# Sheet1.net
KiCad netlist of a schematic drawn in Altium Designer
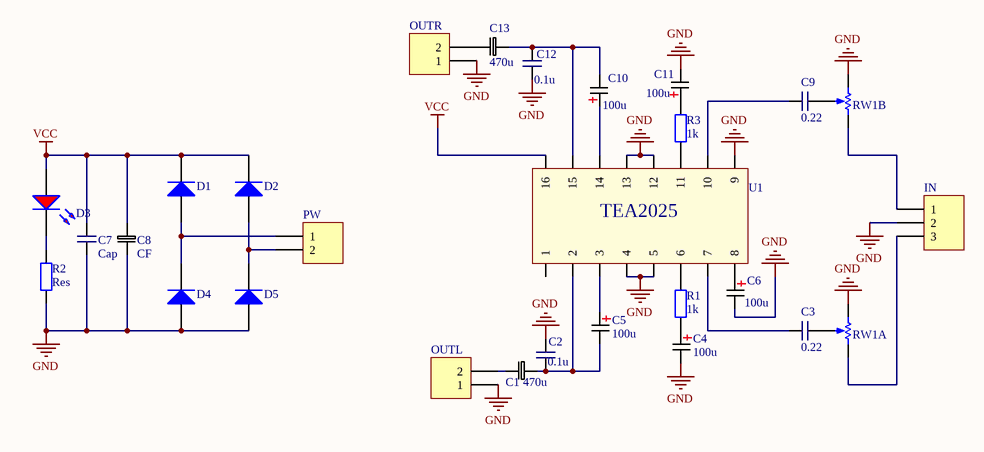
[diagram p0: Sheet1.SchDoc]

(export (version "E")
  (design (tool "Eeschema 10.0.6"))
  (components
    (comp (ref "C1") (value "470u") (footprint "CF0.1-6.5") (libsource (lib "MY") (part "CF")))
    (comp (ref "C2") (value "0.1u") (footprint "RAD0.1") (libsource (lib "MY") (part "Cap")))
    (comp (ref "C3") (value "0.22") (footprint "RAD-0.2") (libsource (lib "MY") (part "Cap")))
    (comp (ref "C4") (value "100u") (footprint "CF0.1") (libsource (lib "MY") (part "Cap Pol")))
    (comp (ref "C5") (value "100u") (footprint "CF0.1") (libsource (lib "MY") (part "Cap Pol")))
    (comp (ref "C6") (value "100u") (footprint "CF0.1") (libsource (lib "MY") (part "Cap Pol")))
    (comp (ref "C7") (value "Cap") (footprint "RAD0.1") (libsource (lib "MY") (part "Cap")))
    (comp (ref "C8") (value "CF") (footprint "CF0.2-13") (libsource (lib "MY") (part "CF")))
    (comp (ref "C9") (value "0.22") (footprint "RAD-0.2") (libsource (lib "MY") (part "Cap")))
    (comp (ref "C10") (value "100u") (footprint "CF0.1") (libsource (lib "MY") (part "Cap Pol")))
    (comp (ref "C11") (value "100u") (footprint "CF0.1") (libsource (lib "MY") (part "Cap Pol")))
    (comp (ref "C12") (value "0.1u") (footprint "RAD0.1") (libsource (lib "MY") (part "Cap")))
    (comp (ref "C13") (value "470u") (footprint "CF0.1-6.5") (libsource (lib "MY") (part "CF")))
    (comp (ref "D1")
      (value "Diode 1N4007")
      (footprint "DIO10.46-5.3x2.8")
      (description "1 Amp General Purpose Rectifier")
      (fields (field (name "PUBLISHER") "Altium Limited"))
      (libsource (lib "Miscellaneous Devices") (part "Diode 1N4007"))
    )
    (comp (ref "D2")
      (value "Diode 1N4007")
      (footprint "DIO10.46-5.3x2.8")
      (description "1 Amp General Purpose Rectifier")
      (fields (field (name "PUBLISHER") "Altium Limited"))
      (libsource (lib "Miscellaneous Devices") (part "Diode 1N4007"))
    )
    (comp (ref "D3")
      (value "LED0")
      (footprint "LED")
      (fields (field (name "PUBLISHER") "Altium Limited"))
      (libsource (lib "MY") (part "LED0"))
    )
    (comp (ref "D4")
      (value "Diode 1N4007")
      (footprint "DIO10.46-5.3x2.8")
      (description "1 Amp General Purpose Rectifier")
      (fields (field (name "PUBLISHER") "Altium Limited"))
      (libsource (lib "Miscellaneous Devices") (part "Diode 1N4007"))
    )
    (comp (ref "D5")
      (value "Diode 1N4007")
      (footprint "DIO10.46-5.3x2.8")
      (description "1 Amp General Purpose Rectifier")
      (fields (field (name "PUBLISHER") "Altium Limited"))
      (libsource (lib "Miscellaneous Devices") (part "Diode 1N4007"))
    )
    (comp (ref "IN")
      (value "~")
      (footprint "HDR1X3")
      (description "Header, 3-Pin, Right Angle")
      (fields (field (name "PUBLISHER") "Altium Limited"))
      (libsource (lib "Miscellaneous Connectors") (part "Header 3H"))
    )
    (comp (ref "OUTL")
      (value "Header 2")
      (footprint "HDR1X2")
      (description "Header, 2-Pin")
      (fields (field (name "PUBLISHER") "Altium Limited"))
      (libsource (lib "Miscellaneous Connectors") (part "Header 2"))
    )
    (comp (ref "OUTR")
      (value "Header 2")
      (footprint "HDR1X2")
      (description "Header, 2-Pin")
      (fields (field (name "PUBLISHER") "Altium Limited"))
      (libsource (lib "Miscellaneous Connectors") (part "Header 2"))
    )
    (comp (ref "PW")
      (value "Header 2")
      (footprint "HDR1X2")
      (description "Header, 2-Pin")
      (fields (field (name "PUBLISHER") "Altium Limited"))
      (libsource (lib "") (part "Header 2_1"))
    )
    (comp (ref "R1")
      (value "1k")
      (footprint "RAD-0.1")
      (description "Resistor")
      (fields (field (name "PUBLISHER") "Altium Limited"))
      (libsource (lib "MY") (part "Res"))
    )
    (comp (ref "R2")
      (value "Res")
      (footprint "AXIAL-0.3")
      (description "Resistor")
      (fields (field (name "PUBLISHER") "Altium Limited"))
      (libsource (lib "") (part "Res_1"))
    )
    (comp (ref "R3")
      (value "1k")
      (footprint "RAD-0.1")
      (description "Resistor")
      (fields (field (name "PUBLISHER") "Altium Limited"))
      (libsource (lib "MY") (part "Res"))
    )
    (comp (ref "RW1") (value "RW") (footprint "RW") (libsource (lib "MY") (part "RW")))
    (comp (ref "U1") (value "TEA2025") (footprint "DIP16") (libsource (lib "MY") (part "TEA2025")))
  )
  (nets
    (net (code "1") (name "GND") (class "Default")
      (node (ref "C11") (pin "2") (pinfunction "2_2") (pintype "passive"))
      (node (ref "C12") (pin "2") (pinfunction "2_2") (pintype "passive"))
      (node (ref "C2") (pin "1") (pinfunction "1_1") (pintype "passive"))
      (node (ref "C4") (pin "2") (pinfunction "2_2") (pintype "passive"))
      (node (ref "C6") (pin "2") (pinfunction "2_2") (pintype "passive"))
      (node (ref "C7") (pin "1") (pinfunction "1_1") (pintype "passive"))
      (node (ref "C8") (pin "2") (pinfunction "2_2") (pintype "passive"))
      (node (ref "D4") (pin "1") (pinfunction "A_1") (pintype "passive"))
      (node (ref "D5") (pin "1") (pinfunction "A_1") (pintype "passive"))
      (node (ref "IN") (pin "2") (pinfunction "2_2") (pintype "passive"))
      (node (ref "OUTL") (pin "1") (pinfunction "1_1") (pintype "passive"))
      (node (ref "OUTR") (pin "1") (pinfunction "1_1") (pintype "passive"))
      (node (ref "R2") (pin "1") (pinfunction "1_1") (pintype "passive"))
      (node (ref "RW1") (pin "1") (pinfunction "TOP_1") (pintype "passive"))
      (node (ref "RW1") (pin "4") (pinfunction "TOP_4") (pintype "passive"))
      (node (ref "U1") (pin "12") (pinfunction "12_12") (pintype "passive"))
      (node (ref "U1") (pin "13") (pinfunction "13_13") (pintype "passive"))
      (node (ref "U1") (pin "4") (pinfunction "4_4") (pintype "passive"))
      (node (ref "U1") (pin "5") (pinfunction "5_5") (pintype "passive"))
      (node (ref "U1") (pin "9") (pinfunction "9_9") (pintype "passive"))
    )
    (net (code "2") (name "Net-(C1-Pad1)") (class "Default")
      (node (ref "C1") (pin "1") (pinfunction "1_1") (pintype "passive"))
      (node (ref "C2") (pin "2") (pinfunction "2_2") (pintype "passive"))
      (node (ref "C5") (pin "2") (pinfunction "2_2") (pintype "passive"))
      (node (ref "U1") (pin "2") (pinfunction "2_2") (pintype "passive"))
    )
    (net (code "3") (name "Net-(C1-Pad2)") (class "Default")
      (node (ref "C1") (pin "2") (pinfunction "2_2") (pintype "passive"))
      (node (ref "OUTL") (pin "2") (pinfunction "2_2") (pintype "passive"))
    )
    (net (code "4") (name "Net-(C3-Pad2)") (class "Default")
      (node (ref "C3") (pin "2") (pinfunction "2_2") (pintype "passive"))
      (node (ref "U1") (pin "7") (pinfunction "7_7") (pintype "passive"))
    )
    (net (code "5") (name "Net-(C4-Pad1)") (class "Default")
      (node (ref "C4") (pin "1") (pinfunction "1_1") (pintype "passive"))
      (node (ref "R1") (pin "2") (pinfunction "2_2") (pintype "passive"))
    )
    (net (code "6") (name "Net-(C5-Pad1)") (class "Default")
      (node (ref "C5") (pin "1") (pinfunction "1_1") (pintype "passive"))
      (node (ref "U1") (pin "3") (pinfunction "3_3") (pintype "passive"))
    )
    (net (code "7") (name "Net-(C6-Pad1)") (class "Default")
      (node (ref "C6") (pin "1") (pinfunction "1_1") (pintype "passive"))
      (node (ref "U1") (pin "8") (pinfunction "8_8") (pintype "passive"))
    )
    (net (code "8") (name "Net-(C9-Pad2)") (class "Default")
      (node (ref "C9") (pin "2") (pinfunction "2_2") (pintype "passive"))
      (node (ref "U1") (pin "10") (pinfunction "10_10") (pintype "passive"))
    )
    (net (code "9") (name "Net-(C10-Pad1)") (class "Default")
      (node (ref "C10") (pin "1") (pinfunction "1_1") (pintype "passive"))
      (node (ref "U1") (pin "14") (pinfunction "14_14") (pintype "passive"))
    )
    (net (code "10") (name "Net-(C10-Pad2)") (class "Default")
      (node (ref "C10") (pin "2") (pinfunction "2_2") (pintype "passive"))
      (node (ref "C12") (pin "1") (pinfunction "1_1") (pintype "passive"))
      (node (ref "C13") (pin "1") (pinfunction "1_1") (pintype "passive"))
      (node (ref "U1") (pin "15") (pinfunction "15_15") (pintype "passive"))
    )
    (net (code "11") (name "Net-(C11-Pad1)") (class "Default")
      (node (ref "C11") (pin "1") (pinfunction "1_1") (pintype "passive"))
      (node (ref "R3") (pin "1") (pinfunction "1_1") (pintype "passive"))
    )
    (net (code "12") (name "Net-(C13-Pad2)") (class "Default")
      (node (ref "C13") (pin "2") (pinfunction "2_2") (pintype "passive"))
      (node (ref "OUTR") (pin "2") (pinfunction "2_2") (pintype "passive"))
    )
    (net (code "13") (name "Net-(D1-A)") (class "Default")
      (node (ref "D1") (pin "1") (pinfunction "A_1") (pintype "passive"))
      (node (ref "D4") (pin "2") (pinfunction "K_2") (pintype "passive"))
      (node (ref "PW") (pin "1") (pinfunction "1_1") (pintype "passive"))
    )
    (net (code "14") (name "Net-(D2-A)") (class "Default")
      (node (ref "D2") (pin "1") (pinfunction "A_1") (pintype "passive"))
      (node (ref "D5") (pin "2") (pinfunction "K_2") (pintype "passive"))
      (node (ref "PW") (pin "2") (pinfunction "2_2") (pintype "passive"))
    )
    (net (code "15") (name "Net-(D3-K)") (class "Default")
      (node (ref "D3") (pin "2") (pinfunction "K_2") (pintype "passive"))
      (node (ref "R2") (pin "2") (pinfunction "2_2") (pintype "passive"))
    )
    (net (code "16") (name "Net-(R1-Pad1)") (class "Default")
      (node (ref "R1") (pin "1") (pinfunction "1_1") (pintype "passive"))
      (node (ref "U1") (pin "6") (pinfunction "6_6") (pintype "passive"))
    )
    (net (code "17") (name "Net-(R3-Pad2)") (class "Default")
      (node (ref "R3") (pin "2") (pinfunction "2_2") (pintype "passive"))
      (node (ref "U1") (pin "11") (pinfunction "11_11") (pintype "passive"))
    )
    (net (code "18") (name "Net-(RW1A-BOT)") (class "Default")
      (node (ref "IN") (pin "3") (pinfunction "3_3") (pintype "passive"))
      (node (ref "RW1") (pin "3") (pinfunction "BOT_3") (pintype "passive"))
    )
    (net (code "19") (name "Net-(RW1A-TAP)") (class "Default")
      (node (ref "C3") (pin "1") (pinfunction "1_1") (pintype "passive"))
      (node (ref "RW1") (pin "2") (pinfunction "TAP_2") (pintype "passive"))
    )
    (net (code "20") (name "Net-(RW1B-BOT)") (class "Default")
      (node (ref "IN") (pin "1") (pinfunction "1_1") (pintype "passive"))
      (node (ref "RW1") (pin "6") (pinfunction "BOT_6") (pintype "passive"))
    )
    (net (code "21") (name "Net-(RW1B-TAP)") (class "Default")
      (node (ref "C9") (pin "1") (pinfunction "1_1") (pintype "passive"))
      (node (ref "RW1") (pin "5") (pinfunction "TAP_5") (pintype "passive"))
    )
    (net (code "22") (name "VCC") (class "Default")
      (node (ref "C7") (pin "2") (pinfunction "2_2") (pintype "passive"))
      (node (ref "C8") (pin "1") (pinfunction "1_1") (pintype "passive"))
      (node (ref "D1") (pin "2") (pinfunction "K_2") (pintype "passive"))
      (node (ref "D2") (pin "2") (pinfunction "K_2") (pintype "passive"))
      (node (ref "D3") (pin "1") (pinfunction "A_1") (pintype "passive"))
      (node (ref "U1") (pin "16") (pinfunction "16_16") (pintype "passive"))
    )
    (net (code "23") (name "unconnected-(U1-Pad1)") (class "Default")
      (node (ref "U1") (pin "1") (pinfunction "1_1") (pintype "passive"))
    )
  )
)
